# boost_converter.net
KiCad netlist of a schematic drawn in EAGLE
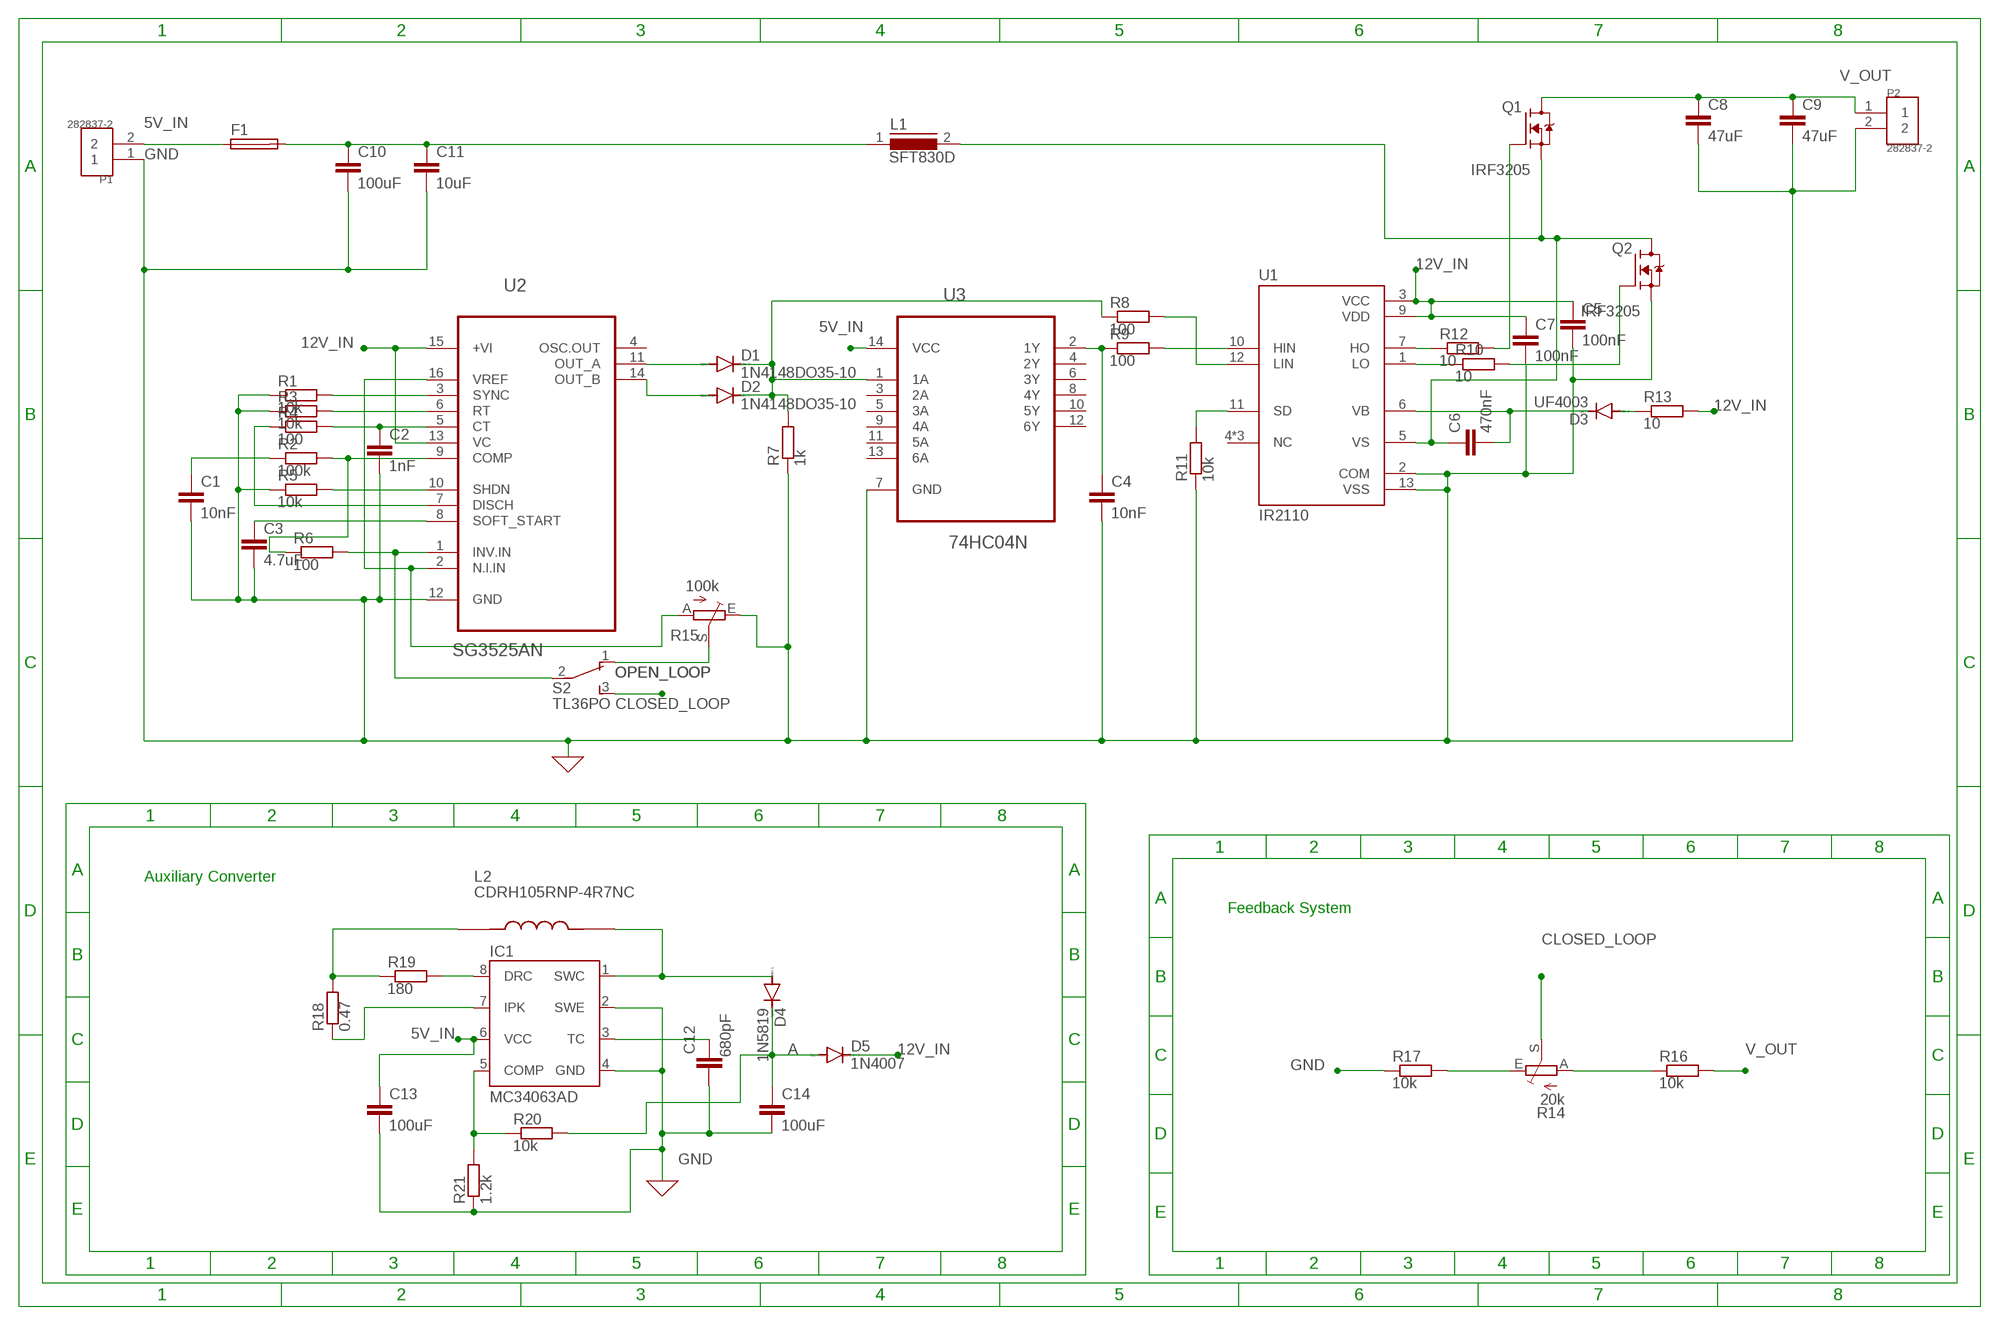
[diagram p0: schematic, sheet 1]

(export (version "E")
  (design (tool "Eeschema 10.0.6"))
  (components
    (comp (ref "C1")
      (value "10nF")
      (footprint "eagle-import:C2.5-3")
      (libsource (lib "eagle-import") (part "C2,5-3"))
    )
    (comp (ref "C2")
      (value "1nF")
      (footprint "eagle-import:C2.5-3")
      (libsource (lib "eagle-import") (part "C2,5-3"))
    )
    (comp (ref "C3")
      (value "4.7uF")
      (footprint "eagle-import:C2.5-5")
      (libsource (lib "eagle-import") (part "C2.5/5"))
    )
    (comp (ref "C4")
      (value "10nF")
      (footprint "eagle-import:C2.5-3")
      (libsource (lib "eagle-import") (part "C2,5-3"))
    )
    (comp (ref "C5")
      (value "100nF")
      (footprint "eagle-import:C2.5-3")
      (libsource (lib "eagle-import") (part "C2,5-3"))
    )
    (comp (ref "C6")
      (value "470nF")
      (footprint "eagle-import:C2.5-3")
      (libsource (lib "eagle-import") (part "C2,5-3"))
    )
    (comp (ref "C7")
      (value "100nF")
      (footprint "eagle-import:C2.5-3")
      (libsource (lib "eagle-import") (part "C2,5-3"))
    )
    (comp (ref "C8")
      (value "47uF")
      (footprint "eagle-import:C2.5-5")
      (libsource (lib "eagle-import") (part "C2.5/5"))
    )
    (comp (ref "C9")
      (value "47uF")
      (footprint "eagle-import:C2.5-5")
      (libsource (lib "eagle-import") (part "C2.5/5"))
    )
    (comp (ref "C10")
      (value "100uF")
      (footprint "eagle-import:C2.5-5")
      (libsource (lib "eagle-import") (part "C2.5/5"))
    )
    (comp (ref "C11")
      (value "10uF")
      (footprint "eagle-import:C2.5-5")
      (libsource (lib "eagle-import") (part "C2.5/5"))
    )
    (comp (ref "C12")
      (value "680pF")
      (footprint "eagle-import:C2.5-3")
      (libsource (lib "eagle-import") (part "C2,5-3"))
    )
    (comp (ref "C13")
      (value "100uF")
      (footprint "eagle-import:C2.5-5")
      (libsource (lib "eagle-import") (part "C2.5/5"))
    )
    (comp (ref "C14")
      (value "100uF")
      (footprint "eagle-import:C2.5-5")
      (libsource (lib "eagle-import") (part "C2.5/5"))
    )
    (comp (ref "D1")
      (value "1N4148DO35-10")
      (footprint "eagle-import:DO35-10")
      (libsource (lib "eagle-import") (part "1N4148DO35-10"))
    )
    (comp (ref "D2")
      (value "1N4148DO35-10")
      (footprint "eagle-import:DO35-10")
      (libsource (lib "eagle-import") (part "1N4148DO35-10"))
    )
    (comp (ref "D3")
      (value "UF4003")
      (footprint "eagle-import:DO41-10")
      (libsource (lib "eagle-import") (part "UF4003"))
    )
    (comp (ref "D4")
      (value "1N5819")
      (footprint "eagle-import:DO41-10")
      (libsource (lib "eagle-import") (part "1N4933"))
    )
    (comp (ref "D5")
      (value "1N4007")
      (footprint "eagle-import:DO41-10")
      (libsource (lib "eagle-import") (part "1N4004"))
    )
    (comp (ref "F1")
      (value "GSH15")
      (footprint "eagle-import:GSH15")
      (fields (field (name "MPN") "64900001039"))
      (libsource (lib "eagle-import") (part "GSH15"))
    )
    (comp (ref "IC1")
      (value "MC34063AD")
      (footprint "eagle-import:SO08")
      (fields (field (name "MF") "Texas Instruments") (field (name "MP") "MC34063A"))
      (libsource (lib "eagle-import") (part "MC34063AD"))
    )
    (comp (ref "L1")
      (value "SFT830D")
      (footprint "eagle-import:SFT830D")
      (libsource (lib "eagle-import") (part "SFT830D"))
    )
    (comp (ref "L2")
      (value "CDRH105RNP-4R7NC")
      (footprint "eagle-import:IND_CDRH105RNP-4R7NC")
      (fields (field (name "MF") "Sumida"))
      (libsource (lib "eagle-import") (part "CDRH105RNP-4R7NC"))
    )
    (comp (ref "P1")
      (value "282837-2")
      (footprint "eagle-import:TE_282837-2")
      (fields (field (name "MF") "TE Connectivity"))
      (libsource (lib "eagle-import") (part "282837-2"))
    )
    (comp (ref "P2")
      (value "282837-2")
      (footprint "eagle-import:TE_282837-2")
      (fields (field (name "MF") "TE Connectivity"))
      (libsource (lib "eagle-import") (part "282837-2"))
    )
    (comp (ref "Q1")
      (value "IRF3205")
      (footprint "eagle-import:TO254P1041X444X2933-3")
      (fields (field (name "MF") "Infineon Technologies"))
      (libsource (lib "eagle-import") (part "IRF3205"))
    )
    (comp (ref "Q2")
      (value "IRF3205")
      (footprint "eagle-import:TO254P1041X444X2933-3")
      (fields (field (name "MF") "Infineon Technologies"))
      (libsource (lib "eagle-import") (part "IRF3205"))
    )
    (comp (ref "R1")
      (value "10k")
      (footprint "eagle-import:0207_10")
      (libsource (lib "eagle-import") (part "R-EU_0207/10"))
    )
    (comp (ref "R2")
      (value "100k")
      (footprint "eagle-import:0207_10")
      (libsource (lib "eagle-import") (part "R-EU_0207/10"))
    )
    (comp (ref "R3")
      (value "10k")
      (footprint "eagle-import:0207_10")
      (libsource (lib "eagle-import") (part "R-EU_0207/10"))
    )
    (comp (ref "R4")
      (value "100")
      (footprint "eagle-import:0207_10")
      (libsource (lib "eagle-import") (part "R-EU_0207/10"))
    )
    (comp (ref "R5")
      (value "10k")
      (footprint "eagle-import:0207_10")
      (libsource (lib "eagle-import") (part "R-EU_0207/10"))
    )
    (comp (ref "R6")
      (value "100")
      (footprint "eagle-import:0207_10")
      (libsource (lib "eagle-import") (part "R-EU_0207/10"))
    )
    (comp (ref "R7")
      (value "1k")
      (footprint "eagle-import:0207_10")
      (libsource (lib "eagle-import") (part "R-EU_0207/10"))
    )
    (comp (ref "R8")
      (value "100")
      (footprint "eagle-import:0207_10")
      (libsource (lib "eagle-import") (part "R-EU_0207/10"))
    )
    (comp (ref "R9")
      (value "100")
      (footprint "eagle-import:0207_10")
      (libsource (lib "eagle-import") (part "R-EU_0207/10"))
    )
    (comp (ref "R10")
      (value "10")
      (footprint "eagle-import:0207_10")
      (libsource (lib "eagle-import") (part "R-EU_0207/10"))
    )
    (comp (ref "R11")
      (value "10k")
      (footprint "eagle-import:0207_10")
      (libsource (lib "eagle-import") (part "R-EU_0207/10"))
    )
    (comp (ref "R12")
      (value "10")
      (footprint "eagle-import:0207_10")
      (libsource (lib "eagle-import") (part "R-EU_0207/10"))
    )
    (comp (ref "R13")
      (value "10")
      (footprint "eagle-import:0207_10")
      (libsource (lib "eagle-import") (part "R-EU_0207/10"))
    )
    (comp (ref "R14")
      (value "20k")
      (footprint "eagle-import:S64W")
      (libsource (lib "eagle-import") (part "TRIM_EU-S64W"))
    )
    (comp (ref "R15")
      (value "100k")
      (footprint "eagle-import:S64W")
      (libsource (lib "eagle-import") (part "TRIM_EU-S64W"))
    )
    (comp (ref "R16")
      (value "10k")
      (footprint "eagle-import:0309_10")
      (libsource (lib "eagle-import") (part "R-EU_0309/10"))
    )
    (comp (ref "R17")
      (value "10k")
      (footprint "eagle-import:0309_10")
      (libsource (lib "eagle-import") (part "R-EU_0309/10"))
    )
    (comp (ref "R18")
      (value "0.47")
      (footprint "eagle-import:0207_10")
      (libsource (lib "eagle-import") (part "R-EU_0207/10"))
    )
    (comp (ref "R19")
      (value "180")
      (footprint "eagle-import:0207_10")
      (libsource (lib "eagle-import") (part "R-EU_0207/10"))
    )
    (comp (ref "R20")
      (value "10k")
      (footprint "eagle-import:0207_10")
      (libsource (lib "eagle-import") (part "R-EU_0207/10"))
    )
    (comp (ref "R21")
      (value "1.2k")
      (footprint "eagle-import:0207_10")
      (libsource (lib "eagle-import") (part "R-EU_0207/10"))
    )
    (comp (ref "S2")
      (value "TL36PO")
      (footprint "eagle-import:TL3XPO")
      (libsource (lib "eagle-import") (part "TL36PO"))
    )
    (comp (ref "U1")
      (value "IR2110")
      (footprint "eagle-import:DIP762W45P254L2019H533Q14")
      (fields (field (name "MF") "Infineon"))
      (libsource (lib "eagle-import") (part "IR2110"))
    )
    (comp (ref "U2")
      (value "SG3525AN")
      (footprint "eagle-import:DIP254P762X510-16")
      (fields (field (name "MF") "STMicroelectronics"))
      (libsource (lib "eagle-import") (part "SG3525AN"))
    )
    (comp (ref "U3")
      (value "74HC04N")
      (footprint "eagle-import:DIP254P762X420-14")
      (fields (field (name "MF") "Texas Instruments"))
      (libsource (lib "eagle-import") (part "74HC04N"))
    )
  )
  (nets
    (net (code "1") (name "/5V_IN") (class "Default")
      (node (ref "C10") (pin "1") (pinfunction "1_1") (pintype "passive"))
      (node (ref "C11") (pin "1") (pinfunction "1_1") (pintype "passive"))
      (node (ref "C13") (pin "1") (pinfunction "1_1") (pintype "passive"))
      (node (ref "F1") (pin "1") (pinfunction "1_1") (pintype "passive"))
      (node (ref "F1") (pin "2") (pinfunction "2_2") (pintype "passive"))
      (node (ref "IC1") (pin "6") (pinfunction "VCC_6") (pintype "power_in"))
      (node (ref "L1") (pin "1") (pinfunction "1_1") (pintype "passive"))
      (node (ref "P1") (pin "2") (pinfunction "2_2") (pintype "passive"))
      (node (ref "U3") (pin "14") (pinfunction "VCC_14") (pintype "power_in"))
    )
    (net (code "2") (name "/12V_IN") (class "Default")
      (node (ref "C5") (pin "1") (pinfunction "1_1") (pintype "passive"))
      (node (ref "C7") (pin "1") (pinfunction "1_1") (pintype "passive"))
      (node (ref "D5") (pin "C") (pinfunction "C_C") (pintype "passive"))
      (node (ref "R13") (pin "2") (pinfunction "2_2") (pintype "passive"))
      (node (ref "U1") (pin "3") (pinfunction "VCC_3") (pintype "power_in"))
      (node (ref "U1") (pin "9") (pinfunction "VDD_9") (pintype "power_in"))
      (node (ref "U2") (pin "13") (pinfunction "VC_13") (pintype "passive"))
      (node (ref "U2") (pin "15") (pinfunction "+VI_15") (pintype "power_in"))
    )
    (net (code "3") (name "/A") (class "Default")
      (node (ref "C14") (pin "1") (pinfunction "1_1") (pintype "passive"))
      (node (ref "D4") (pin "C") (pinfunction "C_C") (pintype "passive"))
      (node (ref "D5") (pin "A") (pinfunction "A_A") (pintype "passive"))
      (node (ref "R20") (pin "2") (pinfunction "2_2") (pintype "passive"))
    )
    (net (code "4") (name "/CLOSED_LOOP") (class "Default")
      (node (ref "R14") (pin "S") (pinfunction "S_S") (pintype "passive"))
      (node (ref "S2") (pin "3") (pinfunction "S_3") (pintype "passive"))
    )
    (net (code "5") (name "/OPEN_LOOP") (class "Default")
      (node (ref "R15") (pin "S") (pinfunction "S_S") (pintype "passive"))
      (node (ref "S2") (pin "1") (pinfunction "O_1") (pintype "passive"))
    )
    (net (code "6") (name "/V_OUT") (class "Default")
      (node (ref "C8") (pin "1") (pinfunction "1_1") (pintype "passive"))
      (node (ref "C9") (pin "1") (pinfunction "1_1") (pintype "passive"))
      (node (ref "P2") (pin "1") (pinfunction "1_1") (pintype "passive"))
      (node (ref "Q1") (pin "2") (pinfunction "D_2") (pintype "passive"))
      (node (ref "R16") (pin "2") (pinfunction "2_2") (pintype "passive"))
    )
    (net (code "7") (name "GND") (class "Default")
      (node (ref "C1") (pin "2") (pinfunction "2_2") (pintype "passive"))
      (node (ref "C10") (pin "2") (pinfunction "2_2") (pintype "passive"))
      (node (ref "C11") (pin "2") (pinfunction "2_2") (pintype "passive"))
      (node (ref "C12") (pin "1") (pinfunction "1_1") (pintype "passive"))
      (node (ref "C13") (pin "2") (pinfunction "2_2") (pintype "passive"))
      (node (ref "C14") (pin "2") (pinfunction "2_2") (pintype "passive"))
      (node (ref "C2") (pin "2") (pinfunction "2_2") (pintype "passive"))
      (node (ref "C3") (pin "2") (pinfunction "2_2") (pintype "passive"))
      (node (ref "C4") (pin "2") (pinfunction "2_2") (pintype "passive"))
      (node (ref "C5") (pin "2") (pinfunction "2_2") (pintype "passive"))
      (node (ref "C7") (pin "2") (pinfunction "2_2") (pintype "passive"))
      (node (ref "C8") (pin "2") (pinfunction "2_2") (pintype "passive"))
      (node (ref "C9") (pin "2") (pinfunction "2_2") (pintype "passive"))
      (node (ref "IC1") (pin "2") (pinfunction "SWE_2") (pintype "bidirectional"))
      (node (ref "IC1") (pin "4") (pinfunction "GND_4") (pintype "power_in"))
      (node (ref "P1") (pin "1") (pinfunction "1_1") (pintype "passive"))
      (node (ref "P2") (pin "2") (pinfunction "2_2") (pintype "passive"))
      (node (ref "Q2") (pin "3") (pinfunction "S_3") (pintype "passive"))
      (node (ref "R1") (pin "1") (pinfunction "1_1") (pintype "passive"))
      (node (ref "R11") (pin "1") (pinfunction "1_1") (pintype "passive"))
      (node (ref "R15") (pin "E") (pinfunction "E_E") (pintype "passive"))
      (node (ref "R17") (pin "1") (pinfunction "1_1") (pintype "passive"))
      (node (ref "R21") (pin "1") (pinfunction "1_1") (pintype "passive"))
      (node (ref "R3") (pin "1") (pinfunction "1_1") (pintype "passive"))
      (node (ref "R5") (pin "1") (pinfunction "1_1") (pintype "passive"))
      (node (ref "R7") (pin "1") (pinfunction "1_1") (pintype "passive"))
      (node (ref "U1") (pin "13") (pinfunction "VSS_13") (pintype "power_in"))
      (node (ref "U1") (pin "2") (pinfunction "COM_2") (pintype "power_in"))
      (node (ref "U2") (pin "12") (pinfunction "GND_12") (pintype "passive"))
      (node (ref "U3") (pin "7") (pinfunction "GND_7") (pintype "passive"))
    )
    (net (code "8") (name "Net-(C1-Pad1)") (class "Default")
      (node (ref "C1") (pin "1") (pinfunction "1_1") (pintype "passive"))
      (node (ref "R2") (pin "1") (pinfunction "1_1") (pintype "passive"))
    )
    (net (code "9") (name "Net-(D3-PadA)") (class "Default")
      (node (ref "D3") (pin "A") (pinfunction "A_A") (pintype "passive"))
      (node (ref "R13") (pin "1") (pinfunction "1_1") (pintype "passive"))
    )
    (net (code "10") (name "Net-(IC1-COMP)") (class "Default")
      (node (ref "IC1") (pin "5") (pinfunction "COMP_5") (pintype "input"))
      (node (ref "R20") (pin "1") (pinfunction "1_1") (pintype "passive"))
      (node (ref "R21") (pin "2") (pinfunction "2_2") (pintype "passive"))
    )
    (net (code "11") (name "Net-(IC1-DRC)") (class "Default")
      (node (ref "IC1") (pin "8") (pinfunction "DRC_8") (pintype "input"))
      (node (ref "R19") (pin "2") (pinfunction "2_2") (pintype "passive"))
    )
    (net (code "12") (name "Net-(IC1-IPK)") (class "Default")
      (node (ref "IC1") (pin "7") (pinfunction "IPK_7") (pintype "input"))
      (node (ref "R18") (pin "1") (pinfunction "1_1") (pintype "passive"))
    )
    (net (code "13") (name "Net-(IC1-SWC)") (class "Default")
      (node (ref "D4") (pin "A") (pinfunction "A_A") (pintype "passive"))
      (node (ref "IC1") (pin "1") (pinfunction "SWC_1") (pintype "bidirectional"))
      (node (ref "L2") (pin "2") (pinfunction "2_2") (pintype "passive"))
    )
    (net (code "14") (name "Net-(IC1-TC)") (class "Default")
      (node (ref "C12") (pin "2") (pinfunction "2_2") (pintype "passive"))
      (node (ref "IC1") (pin "3") (pinfunction "TC_3") (pintype "passive"))
    )
    (net (code "15") (name "Net-(L2-Pad1)") (class "Default")
      (node (ref "L2") (pin "1") (pinfunction "1_1") (pintype "passive"))
      (node (ref "R18") (pin "2") (pinfunction "2_2") (pintype "passive"))
      (node (ref "R19") (pin "1") (pinfunction "1_1") (pintype "passive"))
    )
    (net (code "16") (name "Net-(Q1-G)") (class "Default")
      (node (ref "Q1") (pin "1") (pinfunction "G_1") (pintype "passive"))
      (node (ref "R12") (pin "2") (pinfunction "2_2") (pintype "passive"))
    )
    (net (code "17") (name "Net-(Q1-S)") (class "Default")
      (node (ref "C6") (pin "1") (pinfunction "1_1") (pintype "passive"))
      (node (ref "L1") (pin "2") (pinfunction "2_2") (pintype "passive"))
      (node (ref "Q1") (pin "3") (pinfunction "S_3") (pintype "passive"))
      (node (ref "Q2") (pin "2") (pinfunction "D_2") (pintype "passive"))
      (node (ref "U1") (pin "5") (pinfunction "VS_5") (pintype "passive"))
    )
    (net (code "18") (name "Net-(Q2-G)") (class "Default")
      (node (ref "Q2") (pin "1") (pinfunction "G_1") (pintype "passive"))
      (node (ref "R10") (pin "2") (pinfunction "2_2") (pintype "passive"))
    )
    (net (code "19") (name "Net-(R14-PadA)") (class "Default")
      (node (ref "R14") (pin "A") (pinfunction "A_A") (pintype "passive"))
      (node (ref "R16") (pin "1") (pinfunction "1_1") (pintype "passive"))
    )
    (net (code "20") (name "Net-(R14-PadE)") (class "Default")
      (node (ref "R14") (pin "E") (pinfunction "E_E") (pintype "passive"))
      (node (ref "R17") (pin "2") (pinfunction "2_2") (pintype "passive"))
    )
    (net (code "21") (name "Net-(S2-P)") (class "Default")
      (node (ref "R6") (pin "2") (pinfunction "2_2") (pintype "passive"))
      (node (ref "S2") (pin "2") (pinfunction "P_2") (pintype "passive"))
      (node (ref "U2") (pin "1") (pinfunction "INV.IN_1") (pintype "input"))
    )
    (net (code "22") (name "Net-(U1-HIN)") (class "Default")
      (node (ref "R9") (pin "2") (pinfunction "2_2") (pintype "passive"))
      (node (ref "U1") (pin "10") (pinfunction "HIN_10") (pintype "input"))
    )
    (net (code "23") (name "Net-(U1-HO)") (class "Default")
      (node (ref "R12") (pin "1") (pinfunction "1_1") (pintype "passive"))
      (node (ref "U1") (pin "7") (pinfunction "HO_7") (pintype "output"))
    )
    (net (code "24") (name "Net-(U1-LIN)") (class "Default")
      (node (ref "R8") (pin "2") (pinfunction "2_2") (pintype "passive"))
      (node (ref "U1") (pin "12") (pinfunction "LIN_12") (pintype "input"))
    )
    (net (code "25") (name "Net-(U1-LO)") (class "Default")
      (node (ref "R10") (pin "1") (pinfunction "1_1") (pintype "passive"))
      (node (ref "U1") (pin "1") (pinfunction "LO_1") (pintype "output"))
    )
    (net (code "26") (name "Net-(U1-SD)") (class "Default")
      (node (ref "R11") (pin "2") (pinfunction "2_2") (pintype "passive"))
      (node (ref "U1") (pin "11") (pinfunction "SD_11") (pintype "input"))
    )
    (net (code "27") (name "Net-(U1-VB)") (class "Default")
      (node (ref "C6") (pin "2") (pinfunction "2_2") (pintype "passive"))
      (node (ref "D3") (pin "C") (pinfunction "C_C") (pintype "passive"))
      (node (ref "U1") (pin "6") (pinfunction "VB_6") (pintype "passive"))
    )
    (net (code "28") (name "Net-(U2-COMP)") (class "Default")
      (node (ref "R2") (pin "2") (pinfunction "2_2") (pintype "passive"))
      (node (ref "R6") (pin "1") (pinfunction "1_1") (pintype "passive"))
      (node (ref "U2") (pin "9") (pinfunction "COMP_9") (pintype "passive"))
    )
    (net (code "29") (name "Net-(U2-CT)") (class "Default")
      (node (ref "C2") (pin "1") (pinfunction "1_1") (pintype "passive"))
      (node (ref "R4") (pin "2") (pinfunction "2_2") (pintype "passive"))
      (node (ref "U2") (pin "5") (pinfunction "CT_5") (pintype "passive"))
    )
    (net (code "30") (name "Net-(U2-DISCH)") (class "Default")
      (node (ref "R4") (pin "1") (pinfunction "1_1") (pintype "passive"))
      (node (ref "U2") (pin "7") (pinfunction "DISCH_7") (pintype "passive"))
    )
    (net (code "31") (name "Net-(U2-N.I.IN)") (class "Default")
      (node (ref "R15") (pin "A") (pinfunction "A_A") (pintype "passive"))
      (node (ref "U2") (pin "16") (pinfunction "VREF_16") (pintype "passive"))
      (node (ref "U2") (pin "2") (pinfunction "N.I.IN_2") (pintype "input"))
    )
    (net (code "32") (name "Net-(U2-OUT_A)") (class "Default")
      (node (ref "D1") (pin "A") (pinfunction "A_A") (pintype "passive"))
      (node (ref "U2") (pin "11") (pinfunction "OUT_A_11") (pintype "output"))
    )
    (net (code "33") (name "Net-(U2-OUT_B)") (class "Default")
      (node (ref "D2") (pin "A") (pinfunction "A_A") (pintype "passive"))
      (node (ref "U2") (pin "14") (pinfunction "OUT_B_14") (pintype "output"))
    )
    (net (code "34") (name "Net-(U2-RT)") (class "Default")
      (node (ref "R3") (pin "2") (pinfunction "2_2") (pintype "passive"))
      (node (ref "U2") (pin "6") (pinfunction "RT_6") (pintype "passive"))
    )
    (net (code "35") (name "Net-(U2-SHDN)") (class "Default")
      (node (ref "R5") (pin "2") (pinfunction "2_2") (pintype "passive"))
      (node (ref "U2") (pin "10") (pinfunction "SHDN_10") (pintype "input"))
    )
    (net (code "36") (name "Net-(U2-SOFT_START)") (class "Default")
      (node (ref "C3") (pin "1") (pinfunction "1_1") (pintype "passive"))
      (node (ref "U2") (pin "8") (pinfunction "SOFT_START_8") (pintype "passive"))
    )
    (net (code "37") (name "Net-(U2-SYNC)") (class "Default")
      (node (ref "R1") (pin "2") (pinfunction "2_2") (pintype "passive"))
      (node (ref "U2") (pin "3") (pinfunction "SYNC_3") (pintype "passive"))
    )
    (net (code "38") (name "Net-(U3-1A)") (class "Default")
      (node (ref "D1") (pin "C") (pinfunction "C_C") (pintype "passive"))
      (node (ref "D2") (pin "C") (pinfunction "C_C") (pintype "passive"))
      (node (ref "R7") (pin "2") (pinfunction "2_2") (pintype "passive"))
      (node (ref "R8") (pin "1") (pinfunction "1_1") (pintype "passive"))
      (node (ref "U3") (pin "1") (pinfunction "1A_1") (pintype "input"))
    )
    (net (code "39") (name "Net-(U3-1Y)") (class "Default")
      (node (ref "C4") (pin "1") (pinfunction "1_1") (pintype "passive"))
      (node (ref "R9") (pin "1") (pinfunction "1_1") (pintype "passive"))
      (node (ref "U3") (pin "2") (pinfunction "1Y_2") (pintype "output"))
    )
    (net (code "40") (name "unconnected-(U1-NC-Pad4)") (class "Default")
      (node (ref "U1") (pin "4") (pinfunction "NC_4") (pintype "no_connect"))
    )
    (net (code "41") (name "unconnected-(U1-NC-Pad8)") (class "Default")
      (node (ref "U1") (pin "8") (pinfunction "NC_8") (pintype "no_connect"))
    )
    (net (code "42") (name "unconnected-(U1-NC-Pad14)") (class "Default")
      (node (ref "U1") (pin "14") (pinfunction "NC_14") (pintype "no_connect"))
    )
    (net (code "43") (name "unconnected-(U2-OSC.OUT-Pad4)") (class "Default")
      (node (ref "U2") (pin "4") (pinfunction "OSC.OUT_4") (pintype "output"))
    )
    (net (code "44") (name "unconnected-(U3-2A-Pad3)") (class "Default")
      (node (ref "U3") (pin "3") (pinfunction "2A_3") (pintype "input"))
    )
    (net (code "45") (name "unconnected-(U3-2Y-Pad4)") (class "Default")
      (node (ref "U3") (pin "4") (pinfunction "2Y_4") (pintype "output"))
    )
    (net (code "46") (name "unconnected-(U3-3A-Pad5)") (class "Default")
      (node (ref "U3") (pin "5") (pinfunction "3A_5") (pintype "input"))
    )
    (net (code "47") (name "unconnected-(U3-3Y-Pad6)") (class "Default")
      (node (ref "U3") (pin "6") (pinfunction "3Y_6") (pintype "output"))
    )
    (net (code "48") (name "unconnected-(U3-4A-Pad9)") (class "Default")
      (node (ref "U3") (pin "9") (pinfunction "4A_9") (pintype "input"))
    )
    (net (code "49") (name "unconnected-(U3-4Y-Pad8)") (class "Default")
      (node (ref "U3") (pin "8") (pinfunction "4Y_8") (pintype "output"))
    )
    (net (code "50") (name "unconnected-(U3-5A-Pad11)") (class "Default")
      (node (ref "U3") (pin "11") (pinfunction "5A_11") (pintype "input"))
    )
    (net (code "51") (name "unconnected-(U3-5Y-Pad10)") (class "Default")
      (node (ref "U3") (pin "10") (pinfunction "5Y_10") (pintype "output"))
    )
    (net (code "52") (name "unconnected-(U3-6A-Pad13)") (class "Default")
      (node (ref "U3") (pin "13") (pinfunction "6A_13") (pintype "input"))
    )
    (net (code "53") (name "unconnected-(U3-6Y-Pad12)") (class "Default")
      (node (ref "U3") (pin "12") (pinfunction "6Y_12") (pintype "output"))
    )
  )
)
